# Mathematical_Function.net
KiCad netlist of a schematic drawn in Altium Designer
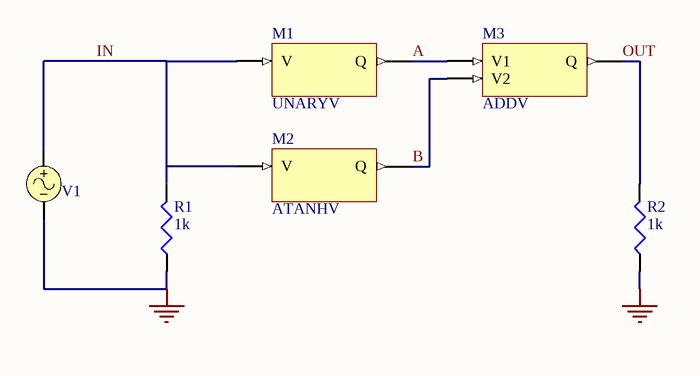
[diagram p0: Mathematical Function.schdoc]

(export (version "E")
  (design (tool "Eeschema 10.0.6"))
  (components
    (comp (ref "M1")
      (value "UNARYV")
      (description "Unary - of Voltage")
      (libsource (lib "*") (part "UNARYV"))
    )
    (comp (ref "M2")
      (value "ATANHV")
      (description "Hyperbolic Arc Tangent of Voltage")
      (libsource (lib "*") (part "ATANHV"))
    )
    (comp (ref "M3") (value "ADDV") (description "Add Voltages") (libsource (lib "*") (part "ADDV")))
    (comp (ref "R1") (value "1k") (description "Resistor") (libsource (lib "*") (part "RES")))
    (comp (ref "R2") (value "1k") (description "Resistor") (libsource (lib "*") (part "RES")))
    (comp (ref "V1")
      (value "VSIN")
      (description "Sinusoidal Voltage Source")
      (libsource (lib "*") (part "VSIN"))
    )
  )
  (nets
    (net (code "1") (name "/A") (class "Default")
      (node (ref "M1") (pin "2") (pinfunction "Q_2") (pintype "output"))
      (node (ref "M3") (pin "1") (pinfunction "V1_1") (pintype "input"))
    )
    (net (code "2") (name "/B") (class "Default")
      (node (ref "M2") (pin "2") (pinfunction "Q_2") (pintype "output"))
      (node (ref "M3") (pin "2") (pinfunction "V2_2") (pintype "input"))
    )
    (net (code "3") (name "/IN") (class "Default")
      (node (ref "M1") (pin "1") (pinfunction "V_1") (pintype "input"))
      (node (ref "M2") (pin "1") (pinfunction "V_1") (pintype "input"))
      (node (ref "R1") (pin "1") (pinfunction "TOP_1") (pintype "passive"))
      (node (ref "V1") (pin "1") (pinfunction "1_1") (pintype "passive"))
    )
    (net (code "4") (name "/OUT") (class "Default")
      (node (ref "M3") (pin "3") (pinfunction "Q_3") (pintype "output"))
      (node (ref "R2") (pin "1") (pinfunction "TOP_1") (pintype "passive"))
    )
    (net (code "5") (name "GND") (class "Default")
      (node (ref "R1") (pin "2") (pinfunction "BOT_2") (pintype "passive"))
      (node (ref "R2") (pin "2") (pinfunction "BOT_2") (pintype "passive"))
      (node (ref "V1") (pin "2") (pinfunction "2_2") (pintype "passive"))
    )
  )
)
